# Connectors_-_Digital.net
KiCad netlist of a schematic drawn in Altium Designer
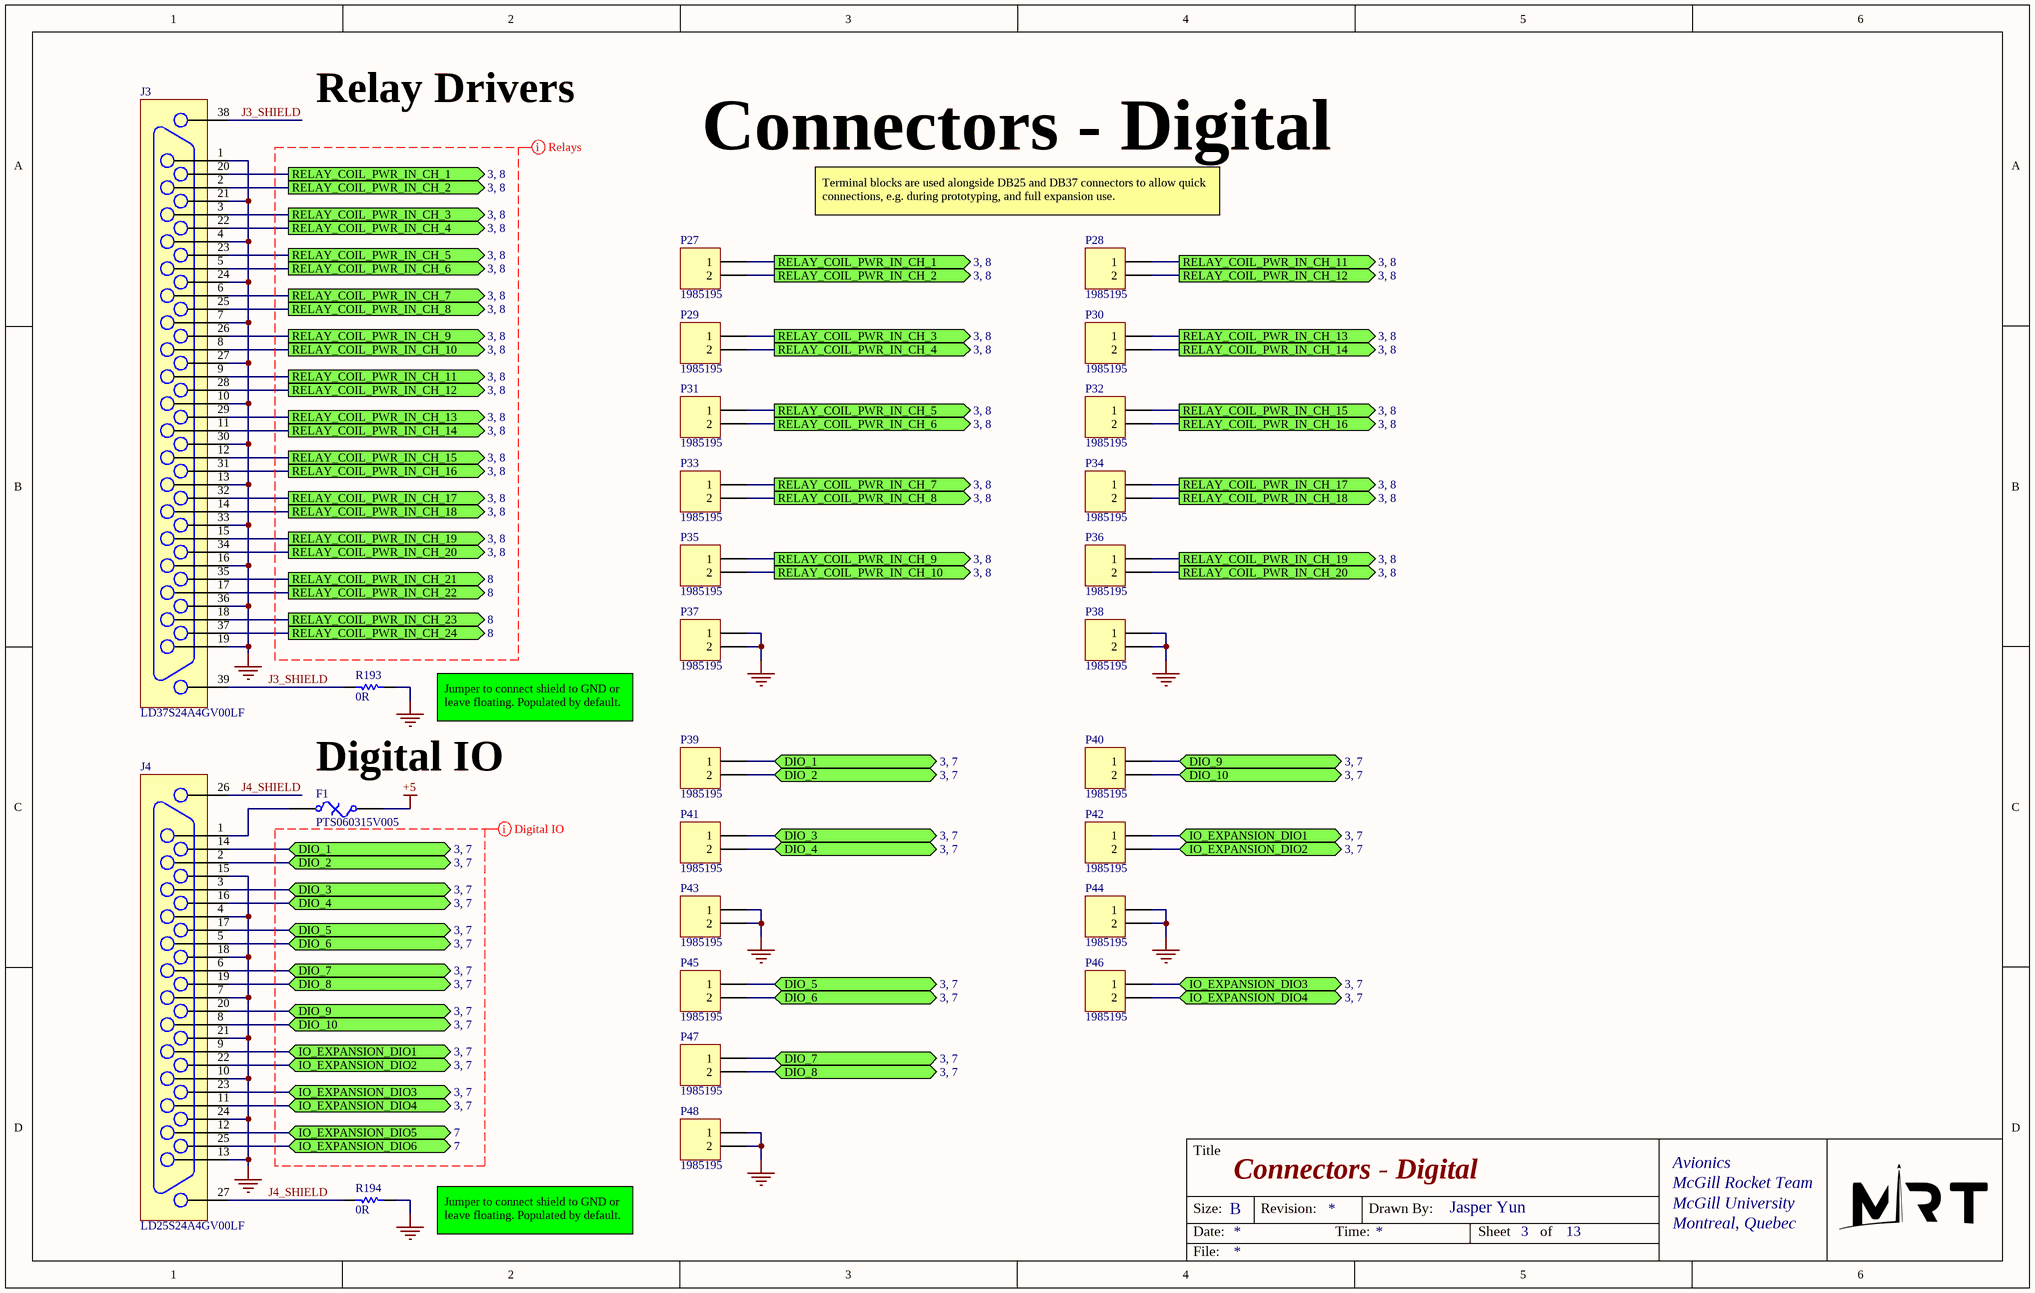
[diagram p0: Connectors - Digital.SchDoc]

(export (version "E")
  (design (tool "Eeschema 10.0.6"))
  (components
    (comp (ref "F1")
      (value "PTS060315V005")
      (footprint "Fuse Thermal 0603 PTS060315V005")
      (description "Thermal Fuse")
      (fields (field (name "PUBLISHER") "Altium Limited"))
      (libsource (lib "Miscellaneous Devices") (part "Fuse Thermal"))
    )
    (comp (ref "J3")
      (value "LD37S24A4GV00LF")
      (footprint "Connector DB37 Vertical LD37S24A4GV00LF")
      (description "DB37 LD37S24A4GV00LF (Amphenol ICC)")
      (libsource (lib "MRT SCH Library") (part "Connector DB37 (LD37S24A4GV00LF)"))
    )
    (comp (ref "J4")
      (value "LD25S24A4GV00LF")
      (footprint "Connector DB25 Vertical LD25S24A4GV00LF")
      (description "DB25 LD25S24A4GV00LF (Amphenol ICC)")
      (libsource (lib "MRT SCH Library") (part "Connector DB25 (LD25S24A4GV00LF)"))
    )
    (comp (ref "P27")
      (value "1985195")
      (footprint "Terminal Block 1985195 2-pos 3.5mm pitch")
      (description "Header, 2-Pin")
      (fields (field (name "PUBLISHER") "Altium Limited"))
      (libsource (lib "Miscellaneous Connectors") (part "Header 2"))
    )
    (comp (ref "P28")
      (value "1985195")
      (footprint "Terminal Block 1985195 2-pos 3.5mm pitch")
      (description "Header, 2-Pin")
      (fields (field (name "PUBLISHER") "Altium Limited"))
      (libsource (lib "Miscellaneous Connectors") (part "Header 2"))
    )
    (comp (ref "P29")
      (value "1985195")
      (footprint "Terminal Block 1985195 2-pos 3.5mm pitch")
      (description "Header, 2-Pin")
      (fields (field (name "PUBLISHER") "Altium Limited"))
      (libsource (lib "Miscellaneous Connectors") (part "Header 2"))
    )
    (comp (ref "P30")
      (value "1985195")
      (footprint "Terminal Block 1985195 2-pos 3.5mm pitch")
      (description "Header, 2-Pin")
      (fields (field (name "PUBLISHER") "Altium Limited"))
      (libsource (lib "Miscellaneous Connectors") (part "Header 2"))
    )
    (comp (ref "P31")
      (value "1985195")
      (footprint "Terminal Block 1985195 2-pos 3.5mm pitch")
      (description "Header, 2-Pin")
      (fields (field (name "PUBLISHER") "Altium Limited"))
      (libsource (lib "Miscellaneous Connectors") (part "Header 2"))
    )
    (comp (ref "P32")
      (value "1985195")
      (footprint "Terminal Block 1985195 2-pos 3.5mm pitch")
      (description "Header, 2-Pin")
      (fields (field (name "PUBLISHER") "Altium Limited"))
      (libsource (lib "Miscellaneous Connectors") (part "Header 2"))
    )
    (comp (ref "P33")
      (value "1985195")
      (footprint "Terminal Block 1985195 2-pos 3.5mm pitch")
      (description "Header, 2-Pin")
      (fields (field (name "PUBLISHER") "Altium Limited"))
      (libsource (lib "Miscellaneous Connectors") (part "Header 2"))
    )
    (comp (ref "P34")
      (value "1985195")
      (footprint "Terminal Block 1985195 2-pos 3.5mm pitch")
      (description "Header, 2-Pin")
      (fields (field (name "PUBLISHER") "Altium Limited"))
      (libsource (lib "Miscellaneous Connectors") (part "Header 2"))
    )
    (comp (ref "P35")
      (value "1985195")
      (footprint "Terminal Block 1985195 2-pos 3.5mm pitch")
      (description "Header, 2-Pin")
      (fields (field (name "PUBLISHER") "Altium Limited"))
      (libsource (lib "Miscellaneous Connectors") (part "Header 2"))
    )
    (comp (ref "P36")
      (value "1985195")
      (footprint "Terminal Block 1985195 2-pos 3.5mm pitch")
      (description "Header, 2-Pin")
      (fields (field (name "PUBLISHER") "Altium Limited"))
      (libsource (lib "Miscellaneous Connectors") (part "Header 2"))
    )
    (comp (ref "P37")
      (value "1985195")
      (footprint "Terminal Block 1985195 2-pos 3.5mm pitch")
      (description "Header, 2-Pin")
      (fields (field (name "PUBLISHER") "Altium Limited"))
      (libsource (lib "Miscellaneous Connectors") (part "Header 2"))
    )
    (comp (ref "P38")
      (value "1985195")
      (footprint "Terminal Block 1985195 2-pos 3.5mm pitch")
      (description "Header, 2-Pin")
      (fields (field (name "PUBLISHER") "Altium Limited"))
      (libsource (lib "Miscellaneous Connectors") (part "Header 2"))
    )
    (comp (ref "P39")
      (value "1985195")
      (footprint "Terminal Block 1985195 2-pos 3.5mm pitch")
      (description "Header, 2-Pin")
      (fields (field (name "PUBLISHER") "Altium Limited"))
      (libsource (lib "Miscellaneous Connectors") (part "Header 2"))
    )
    (comp (ref "P40")
      (value "1985195")
      (footprint "Terminal Block 1985195 2-pos 3.5mm pitch")
      (description "Header, 2-Pin")
      (fields (field (name "PUBLISHER") "Altium Limited"))
      (libsource (lib "Miscellaneous Connectors") (part "Header 2"))
    )
    (comp (ref "P41")
      (value "1985195")
      (footprint "Terminal Block 1985195 2-pos 3.5mm pitch")
      (description "Header, 2-Pin")
      (fields (field (name "PUBLISHER") "Altium Limited"))
      (libsource (lib "Miscellaneous Connectors") (part "Header 2"))
    )
    (comp (ref "P42")
      (value "1985195")
      (footprint "Terminal Block 1985195 2-pos 3.5mm pitch")
      (description "Header, 2-Pin")
      (fields (field (name "PUBLISHER") "Altium Limited"))
      (libsource (lib "Miscellaneous Connectors") (part "Header 2"))
    )
    (comp (ref "P43")
      (value "1985195")
      (footprint "Terminal Block 1985195 2-pos 3.5mm pitch")
      (description "Header, 2-Pin")
      (fields (field (name "PUBLISHER") "Altium Limited"))
      (libsource (lib "Miscellaneous Connectors") (part "Header 2"))
    )
    (comp (ref "P44")
      (value "1985195")
      (footprint "Terminal Block 1985195 2-pos 3.5mm pitch")
      (description "Header, 2-Pin")
      (fields (field (name "PUBLISHER") "Altium Limited"))
      (libsource (lib "Miscellaneous Connectors") (part "Header 2"))
    )
    (comp (ref "P45")
      (value "1985195")
      (footprint "Terminal Block 1985195 2-pos 3.5mm pitch")
      (description "Header, 2-Pin")
      (fields (field (name "PUBLISHER") "Altium Limited"))
      (libsource (lib "Miscellaneous Connectors") (part "Header 2"))
    )
    (comp (ref "P46")
      (value "1985195")
      (footprint "Terminal Block 1985195 2-pos 3.5mm pitch")
      (description "Header, 2-Pin")
      (fields (field (name "PUBLISHER") "Altium Limited"))
      (libsource (lib "Miscellaneous Connectors") (part "Header 2"))
    )
    (comp (ref "P47")
      (value "1985195")
      (footprint "Terminal Block 1985195 2-pos 3.5mm pitch")
      (description "Header, 2-Pin")
      (fields (field (name "PUBLISHER") "Altium Limited"))
      (libsource (lib "Miscellaneous Connectors") (part "Header 2"))
    )
    (comp (ref "P48")
      (value "1985195")
      (footprint "Terminal Block 1985195 2-pos 3.5mm pitch")
      (description "Header, 2-Pin")
      (fields (field (name "PUBLISHER") "Altium Limited"))
      (libsource (lib "Miscellaneous Connectors") (part "Header 2"))
    )
    (comp (ref "R193")
      (value "0R")
      (footprint "0402 RES")
      (description "Resistor")
      (fields (field (name "PUBLISHER") "Altium Limited"))
      (libsource (lib "Miscellaneous Devices") (part "Res1"))
    )
    (comp (ref "R194")
      (value "0R")
      (footprint "0402 RES")
      (description "Resistor")
      (fields (field (name "PUBLISHER") "Altium Limited"))
      (libsource (lib "Miscellaneous Devices") (part "Res1"))
    )
  )
  (nets
    (net (code "1") (name "+5") (class "Default")
      (node (ref "F1") (pin "2") (pinfunction "2_2") (pintype "passive"))
    )
    (net (code "2") (name "/DIO_1") (class "Default")
      (node (ref "J4") (pin "14") (pinfunction "14_14") (pintype "passive"))
      (node (ref "P39") (pin "1") (pinfunction "1_1") (pintype "passive"))
    )
    (net (code "3") (name "/DIO_2") (class "Default")
      (node (ref "J4") (pin "2") (pinfunction "2_2") (pintype "passive"))
      (node (ref "P39") (pin "2") (pinfunction "2_2") (pintype "passive"))
    )
    (net (code "4") (name "/DIO_3") (class "Default")
      (node (ref "J4") (pin "3") (pinfunction "3_3") (pintype "passive"))
      (node (ref "P41") (pin "1") (pinfunction "1_1") (pintype "passive"))
    )
    (net (code "5") (name "/DIO_4") (class "Default")
      (node (ref "J4") (pin "16") (pinfunction "16_16") (pintype "passive"))
      (node (ref "P41") (pin "2") (pinfunction "2_2") (pintype "passive"))
    )
    (net (code "6") (name "/DIO_5") (class "Default")
      (node (ref "J4") (pin "17") (pinfunction "17_17") (pintype "passive"))
      (node (ref "P45") (pin "1") (pinfunction "1_1") (pintype "passive"))
    )
    (net (code "7") (name "/DIO_6") (class "Default")
      (node (ref "J4") (pin "5") (pinfunction "5_5") (pintype "passive"))
      (node (ref "P45") (pin "2") (pinfunction "2_2") (pintype "passive"))
    )
    (net (code "8") (name "/DIO_7") (class "Default")
      (node (ref "J4") (pin "6") (pinfunction "6_6") (pintype "passive"))
      (node (ref "P47") (pin "1") (pinfunction "1_1") (pintype "passive"))
    )
    (net (code "9") (name "/DIO_8") (class "Default")
      (node (ref "J4") (pin "19") (pinfunction "19_19") (pintype "passive"))
      (node (ref "P47") (pin "2") (pinfunction "2_2") (pintype "passive"))
    )
    (net (code "10") (name "/DIO_9") (class "Default")
      (node (ref "J4") (pin "20") (pinfunction "20_20") (pintype "passive"))
      (node (ref "P40") (pin "1") (pinfunction "1_1") (pintype "passive"))
    )
    (net (code "11") (name "/DIO_10") (class "Default")
      (node (ref "J4") (pin "8") (pinfunction "8_8") (pintype "passive"))
      (node (ref "P40") (pin "2") (pinfunction "2_2") (pintype "passive"))
    )
    (net (code "12") (name "/IO_EXPANSION_DIO1") (class "Default")
      (node (ref "J4") (pin "9") (pinfunction "9_9") (pintype "passive"))
      (node (ref "P42") (pin "1") (pinfunction "1_1") (pintype "passive"))
    )
    (net (code "13") (name "/IO_EXPANSION_DIO2") (class "Default")
      (node (ref "J4") (pin "22") (pinfunction "22_22") (pintype "passive"))
      (node (ref "P42") (pin "2") (pinfunction "2_2") (pintype "passive"))
    )
    (net (code "14") (name "/IO_EXPANSION_DIO3") (class "Default")
      (node (ref "J4") (pin "23") (pinfunction "23_23") (pintype "passive"))
      (node (ref "P46") (pin "1") (pinfunction "1_1") (pintype "passive"))
    )
    (net (code "15") (name "/IO_EXPANSION_DIO4") (class "Default")
      (node (ref "J4") (pin "11") (pinfunction "11_11") (pintype "passive"))
      (node (ref "P46") (pin "2") (pinfunction "2_2") (pintype "passive"))
    )
    (net (code "16") (name "/IO_EXPANSION_DIO5") (class "Default")
      (node (ref "J4") (pin "12") (pinfunction "12_12") (pintype "passive"))
    )
    (net (code "17") (name "/IO_EXPANSION_DIO6") (class "Default")
      (node (ref "J4") (pin "25") (pinfunction "25_25") (pintype "passive"))
    )
    (net (code "18") (name "/J3_SHIELD") (class "Default")
      (node (ref "J3") (pin "38") (pinfunction "38_38") (pintype "passive"))
      (node (ref "J3") (pin "39") (pinfunction "39_39") (pintype "passive"))
      (node (ref "R193") (pin "1") (pinfunction "1_1") (pintype "passive"))
    )
    (net (code "19") (name "/J4_SHIELD") (class "Default")
      (node (ref "J4") (pin "26") (pinfunction "26_26") (pintype "passive"))
      (node (ref "J4") (pin "27") (pinfunction "27_27") (pintype "passive"))
      (node (ref "R194") (pin "1") (pinfunction "1_1") (pintype "passive"))
    )
    (net (code "20") (name "/RELAY_COIL_PWR_IN_CH_1") (class "Default")
      (node (ref "J3") (pin "20") (pinfunction "20_20") (pintype "passive"))
      (node (ref "P27") (pin "1") (pinfunction "1_1") (pintype "passive"))
    )
    (net (code "21") (name "/RELAY_COIL_PWR_IN_CH_2") (class "Default")
      (node (ref "J3") (pin "2") (pinfunction "2_2") (pintype "passive"))
      (node (ref "P27") (pin "2") (pinfunction "2_2") (pintype "passive"))
    )
    (net (code "22") (name "/RELAY_COIL_PWR_IN_CH_3") (class "Default")
      (node (ref "J3") (pin "3") (pinfunction "3_3") (pintype "passive"))
      (node (ref "P29") (pin "1") (pinfunction "1_1") (pintype "passive"))
    )
    (net (code "23") (name "/RELAY_COIL_PWR_IN_CH_4") (class "Default")
      (node (ref "J3") (pin "22") (pinfunction "22_22") (pintype "passive"))
      (node (ref "P29") (pin "2") (pinfunction "2_2") (pintype "passive"))
    )
    (net (code "24") (name "/RELAY_COIL_PWR_IN_CH_5") (class "Default")
      (node (ref "J3") (pin "23") (pinfunction "23_23") (pintype "passive"))
      (node (ref "P31") (pin "1") (pinfunction "1_1") (pintype "passive"))
    )
    (net (code "25") (name "/RELAY_COIL_PWR_IN_CH_6") (class "Default")
      (node (ref "J3") (pin "5") (pinfunction "5_5") (pintype "passive"))
      (node (ref "P31") (pin "2") (pinfunction "2_2") (pintype "passive"))
    )
    (net (code "26") (name "/RELAY_COIL_PWR_IN_CH_7") (class "Default")
      (node (ref "J3") (pin "6") (pinfunction "6_6") (pintype "passive"))
      (node (ref "P33") (pin "1") (pinfunction "1_1") (pintype "passive"))
    )
    (net (code "27") (name "/RELAY_COIL_PWR_IN_CH_8") (class "Default")
      (node (ref "J3") (pin "25") (pinfunction "25_25") (pintype "passive"))
      (node (ref "P33") (pin "2") (pinfunction "2_2") (pintype "passive"))
    )
    (net (code "28") (name "/RELAY_COIL_PWR_IN_CH_9") (class "Default")
      (node (ref "J3") (pin "26") (pinfunction "26_26") (pintype "passive"))
      (node (ref "P35") (pin "1") (pinfunction "1_1") (pintype "passive"))
    )
    (net (code "29") (name "/RELAY_COIL_PWR_IN_CH_10") (class "Default")
      (node (ref "J3") (pin "8") (pinfunction "8_8") (pintype "passive"))
      (node (ref "P35") (pin "2") (pinfunction "2_2") (pintype "passive"))
    )
    (net (code "30") (name "/RELAY_COIL_PWR_IN_CH_11") (class "Default")
      (node (ref "J3") (pin "9") (pinfunction "9_9") (pintype "passive"))
      (node (ref "P28") (pin "1") (pinfunction "1_1") (pintype "passive"))
    )
    (net (code "31") (name "/RELAY_COIL_PWR_IN_CH_12") (class "Default")
      (node (ref "J3") (pin "28") (pinfunction "28_28") (pintype "passive"))
      (node (ref "P28") (pin "2") (pinfunction "2_2") (pintype "passive"))
    )
    (net (code "32") (name "/RELAY_COIL_PWR_IN_CH_13") (class "Default")
      (node (ref "J3") (pin "29") (pinfunction "29_29") (pintype "passive"))
      (node (ref "P30") (pin "1") (pinfunction "1_1") (pintype "passive"))
    )
    (net (code "33") (name "/RELAY_COIL_PWR_IN_CH_14") (class "Default")
      (node (ref "J3") (pin "11") (pinfunction "11_11") (pintype "passive"))
      (node (ref "P30") (pin "2") (pinfunction "2_2") (pintype "passive"))
    )
    (net (code "34") (name "/RELAY_COIL_PWR_IN_CH_15") (class "Default")
      (node (ref "J3") (pin "12") (pinfunction "12_12") (pintype "passive"))
      (node (ref "P32") (pin "1") (pinfunction "1_1") (pintype "passive"))
    )
    (net (code "35") (name "/RELAY_COIL_PWR_IN_CH_16") (class "Default")
      (node (ref "J3") (pin "31") (pinfunction "31_31") (pintype "passive"))
      (node (ref "P32") (pin "2") (pinfunction "2_2") (pintype "passive"))
    )
    (net (code "36") (name "/RELAY_COIL_PWR_IN_CH_17") (class "Default")
      (node (ref "J3") (pin "32") (pinfunction "32_32") (pintype "passive"))
      (node (ref "P34") (pin "1") (pinfunction "1_1") (pintype "passive"))
    )
    (net (code "37") (name "/RELAY_COIL_PWR_IN_CH_18") (class "Default")
      (node (ref "J3") (pin "14") (pinfunction "14_14") (pintype "passive"))
      (node (ref "P34") (pin "2") (pinfunction "2_2") (pintype "passive"))
    )
    (net (code "38") (name "/RELAY_COIL_PWR_IN_CH_19") (class "Default")
      (node (ref "J3") (pin "15") (pinfunction "15_15") (pintype "passive"))
      (node (ref "P36") (pin "1") (pinfunction "1_1") (pintype "passive"))
    )
    (net (code "39") (name "/RELAY_COIL_PWR_IN_CH_20") (class "Default")
      (node (ref "J3") (pin "34") (pinfunction "34_34") (pintype "passive"))
      (node (ref "P36") (pin "2") (pinfunction "2_2") (pintype "passive"))
    )
    (net (code "40") (name "/RELAY_COIL_PWR_IN_CH_21") (class "Default")
      (node (ref "J3") (pin "35") (pinfunction "35_35") (pintype "passive"))
    )
    (net (code "41") (name "/RELAY_COIL_PWR_IN_CH_22") (class "Default")
      (node (ref "J3") (pin "17") (pinfunction "17_17") (pintype "passive"))
    )
    (net (code "42") (name "/RELAY_COIL_PWR_IN_CH_23") (class "Default")
      (node (ref "J3") (pin "18") (pinfunction "18_18") (pintype "passive"))
    )
    (net (code "43") (name "/RELAY_COIL_PWR_IN_CH_24") (class "Default")
      (node (ref "J3") (pin "37") (pinfunction "37_37") (pintype "passive"))
    )
    (net (code "44") (name "GND") (class "Default")
      (node (ref "J3") (pin "1") (pinfunction "1_1") (pintype "passive"))
      (node (ref "J3") (pin "10") (pinfunction "10_10") (pintype "passive"))
      (node (ref "J3") (pin "13") (pinfunction "13_13") (pintype "passive"))
      (node (ref "J3") (pin "16") (pinfunction "16_16") (pintype "passive"))
      (node (ref "J3") (pin "19") (pinfunction "19_19") (pintype "passive"))
      (node (ref "J3") (pin "21") (pinfunction "21_21") (pintype "passive"))
      (node (ref "J3") (pin "24") (pinfunction "24_24") (pintype "passive"))
      (node (ref "J3") (pin "27") (pinfunction "27_27") (pintype "passive"))
      (node (ref "J3") (pin "30") (pinfunction "30_30") (pintype "passive"))
      (node (ref "J3") (pin "33") (pinfunction "33_33") (pintype "passive"))
      (node (ref "J3") (pin "36") (pinfunction "36_36") (pintype "passive"))
      (node (ref "J3") (pin "4") (pinfunction "4_4") (pintype "passive"))
      (node (ref "J3") (pin "7") (pinfunction "7_7") (pintype "passive"))
      (node (ref "J4") (pin "10") (pinfunction "10_10") (pintype "passive"))
      (node (ref "J4") (pin "13") (pinfunction "13_13") (pintype "passive"))
      (node (ref "J4") (pin "15") (pinfunction "15_15") (pintype "passive"))
      (node (ref "J4") (pin "18") (pinfunction "18_18") (pintype "passive"))
      (node (ref "J4") (pin "21") (pinfunction "21_21") (pintype "passive"))
      (node (ref "J4") (pin "24") (pinfunction "24_24") (pintype "passive"))
      (node (ref "J4") (pin "4") (pinfunction "4_4") (pintype "passive"))
      (node (ref "J4") (pin "7") (pinfunction "7_7") (pintype "passive"))
      (node (ref "P37") (pin "1") (pinfunction "1_1") (pintype "passive"))
      (node (ref "P37") (pin "2") (pinfunction "2_2") (pintype "passive"))
      (node (ref "P38") (pin "1") (pinfunction "1_1") (pintype "passive"))
      (node (ref "P38") (pin "2") (pinfunction "2_2") (pintype "passive"))
      (node (ref "P43") (pin "1") (pinfunction "1_1") (pintype "passive"))
      (node (ref "P43") (pin "2") (pinfunction "2_2") (pintype "passive"))
      (node (ref "P44") (pin "1") (pinfunction "1_1") (pintype "passive"))
      (node (ref "P44") (pin "2") (pinfunction "2_2") (pintype "passive"))
      (node (ref "P48") (pin "1") (pinfunction "1_1") (pintype "passive"))
      (node (ref "P48") (pin "2") (pinfunction "2_2") (pintype "passive"))
      (node (ref "R193") (pin "2") (pinfunction "2_2") (pintype "passive"))
      (node (ref "R194") (pin "2") (pinfunction "2_2") (pintype "passive"))
    )
    (net (code "45") (name "Net-(F1-Pad1)") (class "Default")
      (node (ref "F1") (pin "1") (pinfunction "1_1") (pintype "passive"))
      (node (ref "J4") (pin "1") (pinfunction "1_1") (pintype "passive"))
    )
  )
)
